# SCH_5730_Compact_2022-07-11.net
KiCad netlist of a schematic drawn in EasyEDA
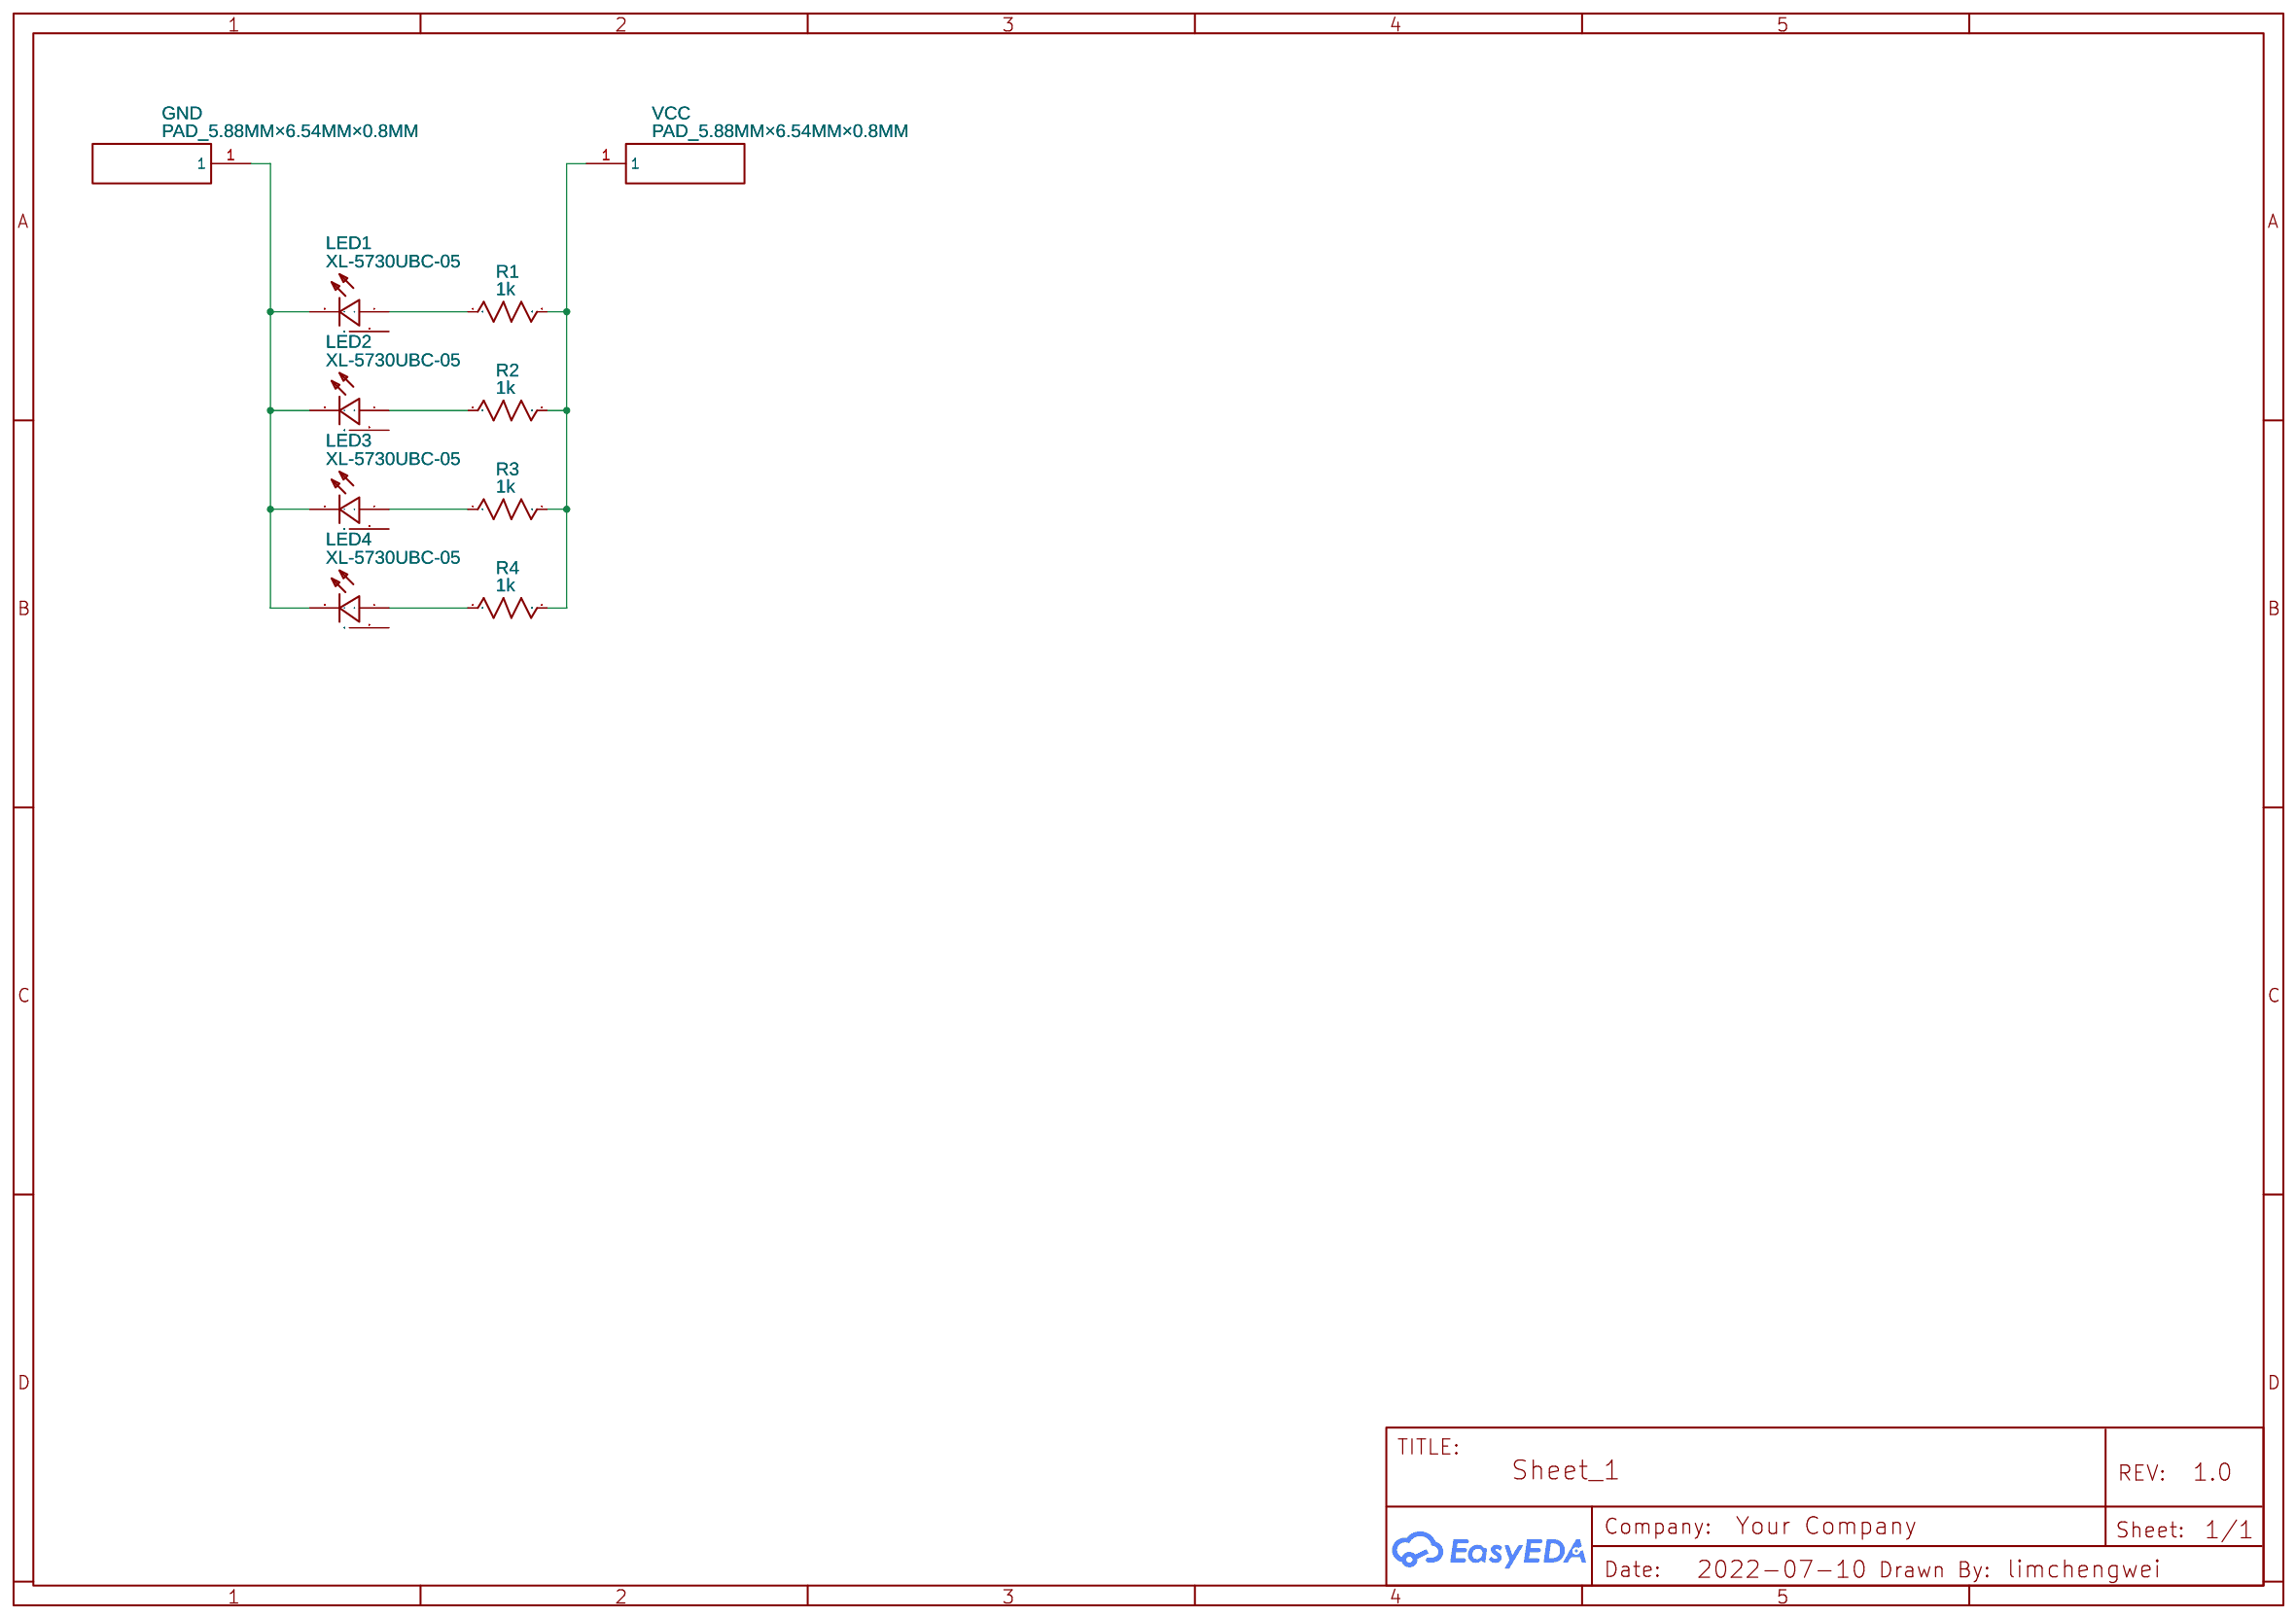
[diagram p0: schematic sheet]

(export (version "E")
  (design (tool "Eeschema 10.0.6"))
  (components
    (comp (ref "GND")
      (value "PAD_5.88MM×6.54MM×0.8MM")
      (fields
        (field (name "BOM_Manufacturer Part") "PAD_5.88mm×6.54mm×0.8mm")
        (field (name "BOM_Supplier Part") "C9900000336")
      )
      (libsource (lib "") (part "PAD_5.88MM×6.54MM×0.8MM_1"))
    )
    (comp (ref "LED1")
      (value "XL-5730UBC-05")
      (fields (field (name "BOM_Supplier Part") "C2843885"))
      (libsource (lib "") (part "XL-5730UBC-05"))
    )
    (comp (ref "LED2")
      (value "XL-5730UBC-05")
      (fields (field (name "BOM_Supplier Part") "C2843885"))
      (libsource (lib "") (part "XL-5730UBC-05"))
    )
    (comp (ref "LED3")
      (value "XL-5730UBC-05")
      (fields (field (name "BOM_Supplier Part") "C2843885"))
      (libsource (lib "") (part "XL-5730UBC-05"))
    )
    (comp (ref "LED4")
      (value "XL-5730UBC-05")
      (fields (field (name "BOM_Supplier Part") "C2843885"))
      (libsource (lib "") (part "XL-5730UBC-05"))
    )
    (comp (ref "R1") (value "1k") (libsource (lib "") (part "R_1812_US")))
    (comp (ref "R2") (value "1k") (libsource (lib "") (part "R_1812_US")))
    (comp (ref "R3") (value "1k") (libsource (lib "") (part "R_1812_US")))
    (comp (ref "R4") (value "1k") (libsource (lib "") (part "R_1812_US")))
    (comp (ref "VCC")
      (value "PAD_5.88MM×6.54MM×0.8MM")
      (fields
        (field (name "BOM_Manufacturer Part") "PAD_5.88mm×6.54mm×0.8mm")
        (field (name "BOM_Supplier Part") "C9900000336")
      )
      (libsource (lib "") (part "PAD_5.88MM×6.54MM×0.8MM"))
    )
  )
  (nets
    (net (code "1") (name "Net-(LED1-+)") (class "Default")
      (node (ref "LED1") (pin "1") (pinfunction "+_1") (pintype "unspecified"))
      (node (ref "R1") (pin "1") (pinfunction "1_1") (pintype "unspecified"))
    )
    (net (code "2") (name "Net-(LED1--)") (class "Default")
      (node (ref "GND") (pin "1") (pinfunction "1_1") (pintype "unspecified"))
      (node (ref "LED1") (pin "2") (pinfunction "-_2") (pintype "unspecified"))
      (node (ref "LED2") (pin "2") (pinfunction "-_2") (pintype "unspecified"))
      (node (ref "LED3") (pin "2") (pinfunction "-_2") (pintype "unspecified"))
      (node (ref "LED4") (pin "2") (pinfunction "-_2") (pintype "unspecified"))
    )
    (net (code "3") (name "Net-(LED2-+)") (class "Default")
      (node (ref "LED2") (pin "1") (pinfunction "+_1") (pintype "unspecified"))
      (node (ref "R2") (pin "1") (pinfunction "1_1") (pintype "unspecified"))
    )
    (net (code "4") (name "Net-(LED3-+)") (class "Default")
      (node (ref "LED3") (pin "1") (pinfunction "+_1") (pintype "unspecified"))
      (node (ref "R3") (pin "1") (pinfunction "1_1") (pintype "unspecified"))
    )
    (net (code "5") (name "Net-(LED4-+)") (class "Default")
      (node (ref "LED4") (pin "1") (pinfunction "+_1") (pintype "unspecified"))
      (node (ref "R4") (pin "1") (pinfunction "1_1") (pintype "unspecified"))
    )
    (net (code "6") (name "Net-(R1-Pad2)") (class "Default")
      (node (ref "R1") (pin "2") (pinfunction "2_2") (pintype "unspecified"))
      (node (ref "R2") (pin "2") (pinfunction "2_2") (pintype "unspecified"))
      (node (ref "R3") (pin "2") (pinfunction "2_2") (pintype "unspecified"))
      (node (ref "R4") (pin "2") (pinfunction "2_2") (pintype "unspecified"))
      (node (ref "VCC") (pin "1") (pinfunction "1_1") (pintype "unspecified"))
    )
    (net (code "7") (name "unconnected-(LED1-Pad3)") (class "Default")
      (node (ref "LED1") (pin "3") (pinfunction "3_3") (pintype "unspecified"))
    )
    (net (code "8") (name "unconnected-(LED2-Pad3)") (class "Default")
      (node (ref "LED2") (pin "3") (pinfunction "3_3") (pintype "unspecified"))
    )
    (net (code "9") (name "unconnected-(LED3-Pad3)") (class "Default")
      (node (ref "LED3") (pin "3") (pinfunction "3_3") (pintype "unspecified"))
    )
    (net (code "10") (name "unconnected-(LED4-Pad3)") (class "Default")
      (node (ref "LED4") (pin "3") (pinfunction "3_3") (pintype "unspecified"))
    )
  )
)
